# breakout_KL27Z_QFP64.net
KiCad netlist of a schematic drawn in EAGLE
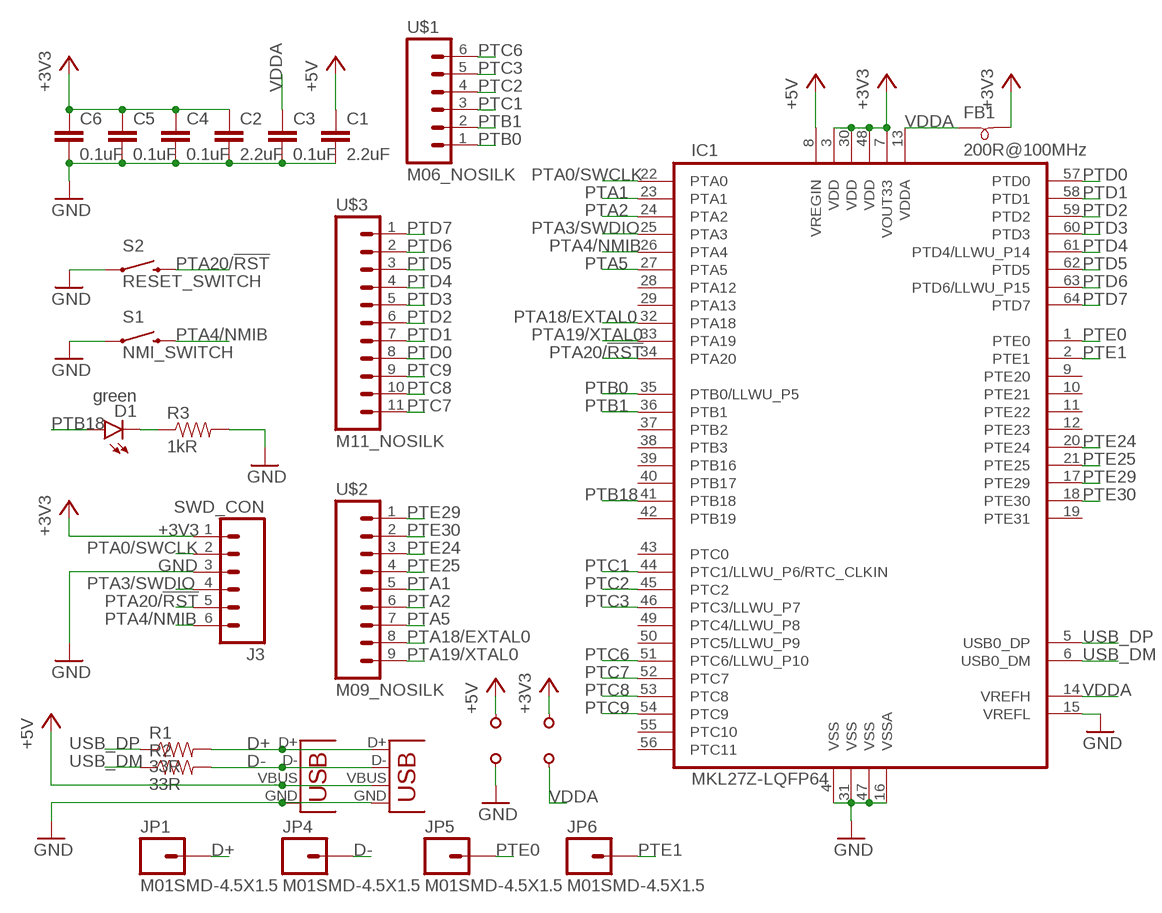
[diagram p0: schematic, sheet 1]

(export (version "E")
  (design (tool "Eeschema 10.0.6"))
  (components
    (comp (ref "C1")
      (value "2.2uF")
      (footprint "eagle-import:0805")
      (libsource (lib "eagle-import") (part "CAPACITOR0805"))
    )
    (comp (ref "C2")
      (value "2.2uF")
      (footprint "eagle-import:0805")
      (libsource (lib "eagle-import") (part "CAPACITOR0805"))
    )
    (comp (ref "C3")
      (value "0.1uF")
      (footprint "eagle-import:0805")
      (libsource (lib "eagle-import") (part "CAPACITOR0805"))
    )
    (comp (ref "C4")
      (value "0.1uF")
      (footprint "eagle-import:0805")
      (libsource (lib "eagle-import") (part "CAPACITOR0805"))
    )
    (comp (ref "C5")
      (value "0.1uF")
      (footprint "eagle-import:0805")
      (libsource (lib "eagle-import") (part "CAPACITOR0805"))
    )
    (comp (ref "C6")
      (value "0.1uF")
      (footprint "eagle-import:0805")
      (libsource (lib "eagle-import") (part "CAPACITOR0805"))
    )
    (comp (ref "D1")
      (value "green")
      (footprint "eagle-import:LED-805")
      (libsource (lib "eagle-import") (part "LED805"))
    )
    (comp (ref "FB1")
      (value "200R@100MHz")
      (footprint "eagle-import:0805")
      (libsource (lib "eagle-import") (part "FERRITE-BEAD0805"))
    )
    (comp (ref "IC1")
      (value "MKL27Z-LQFP64")
      (footprint "eagle-import:TQFP-64-0.5")
      (libsource (lib "eagle-import") (part "MKL27Z-LQFP64"))
    )
    (comp (ref "J3")
      (value "SWD_CON")
      (footprint "eagle-import:M06_NOSILK_1SQ")
      (libsource (lib "eagle-import") (part "M06_NOSILK_1SQ"))
    )
    (comp (ref "JP1")
      (value "M01SMD-4.5X1.5")
      (footprint "eagle-import:PAD-1.5X4.5")
      (libsource (lib "eagle-import") (part "M01SMD-4.5X1.5"))
    )
    (comp (ref "JP2")
      (value "USBSMD")
      (footprint "eagle-import:USB-MINIB")
      (libsource (lib "eagle-import") (part "USBSMD"))
    )
    (comp (ref "JP3")
      (value "USB-MICROB")
      (footprint "eagle-import:USB-MICROB")
      (libsource (lib "eagle-import") (part "USB-MICROB"))
    )
    (comp (ref "JP4")
      (value "M01SMD-4.5X1.5")
      (footprint "eagle-import:PAD-1.5X4.5")
      (libsource (lib "eagle-import") (part "M01SMD-4.5X1.5"))
    )
    (comp (ref "JP5")
      (value "M01SMD-4.5X1.5")
      (footprint "eagle-import:PAD-1.5X4.5")
      (libsource (lib "eagle-import") (part "M01SMD-4.5X1.5"))
    )
    (comp (ref "JP6")
      (value "M01SMD-4.5X1.5")
      (footprint "eagle-import:PAD-1.5X4.5")
      (libsource (lib "eagle-import") (part "M01SMD-4.5X1.5"))
    )
    (comp (ref "R1")
      (value "33R")
      (footprint "eagle-import:0805")
      (libsource (lib "eagle-import") (part "RESISTOR0805"))
    )
    (comp (ref "R2")
      (value "33R")
      (footprint "eagle-import:0805")
      (libsource (lib "eagle-import") (part "RESISTOR0805"))
    )
    (comp (ref "R3")
      (value "1kR")
      (footprint "eagle-import:0805")
      (libsource (lib "eagle-import") (part "RESISTOR0805"))
    )
    (comp (ref "S1")
      (value "NMI_SWITCH")
      (footprint "eagle-import:TACTILE-SWITCH-SMD")
      (libsource (lib "eagle-import") (part "SWITCH-MOMENTARY-2SMD-REDUNDANT"))
    )
    (comp (ref "S2")
      (value "RESET_SWITCH")
      (footprint "eagle-import:TACTILE-SWITCH-SMD")
      (libsource (lib "eagle-import") (part "SWITCH-MOMENTARY-2SMD-REDUNDANT"))
    )
    (comp (ref "U$1")
      (value "M06_NOSILK")
      (footprint "eagle-import:M06_NOSILK")
      (libsource (lib "eagle-import") (part "M06_NOSILK"))
    )
    (comp (ref "U$2")
      (value "M09_NOSILK")
      (footprint "eagle-import:M09_NOSILK")
      (libsource (lib "eagle-import") (part "M09_NOSILK"))
    )
    (comp (ref "U$3")
      (value "M11_NOSILK")
      (footprint "eagle-import:M11_NOSILK")
      (libsource (lib "eagle-import") (part "M11_NOSILK"))
    )
    (comp (ref "U$4")
      (value "M01_1SQ")
      (footprint "eagle-import:M01_1SQ")
      (libsource (lib "eagle-import") (part "M01_1SQ"))
    )
    (comp (ref "U$5")
      (value "M01_1SQ")
      (footprint "eagle-import:M01_1SQ")
      (libsource (lib "eagle-import") (part "M01_1SQ"))
    )
    (comp (ref "U$6")
      (value "M01_NOSILK")
      (footprint "eagle-import:M01_NOSILK")
      (libsource (lib "eagle-import") (part "M01_NOSILK"))
    )
    (comp (ref "U$7")
      (value "M01_1SQ")
      (footprint "eagle-import:M01_1SQ")
      (libsource (lib "eagle-import") (part "M01_1SQ"))
    )
  )
  (nets
    (net (code "1") (name "+3V3") (class "Default")
      (node (ref "C2") (pin "1") (pinfunction "1_1") (pintype "passive"))
      (node (ref "C4") (pin "1") (pinfunction "1_1") (pintype "passive"))
      (node (ref "C5") (pin "1") (pinfunction "1_1") (pintype "passive"))
      (node (ref "C6") (pin "1") (pinfunction "1_1") (pintype "passive"))
      (node (ref "FB1") (pin "2") (pinfunction "2_2") (pintype "passive"))
      (node (ref "IC1") (pin "3") (pinfunction "VDD_3") (pintype "power_in"))
      (node (ref "IC1") (pin "30") (pinfunction "VDD_30") (pintype "power_in"))
      (node (ref "IC1") (pin "48") (pinfunction "VDD_48") (pintype "power_in"))
      (node (ref "IC1") (pin "7") (pinfunction "VOUT33_7") (pintype "power_in"))
      (node (ref "J3") (pin "1") (pinfunction "1_1") (pintype "passive"))
      (node (ref "U$5") (pin "1") (pinfunction "1_1") (pintype "bidirectional"))
    )
    (net (code "2") (name "+5V") (class "Default")
      (node (ref "C1") (pin "1") (pinfunction "1_1") (pintype "passive"))
      (node (ref "IC1") (pin "8") (pinfunction "VREGIN_8") (pintype "power_in"))
      (node (ref "JP2") (pin "VBUS") (pinfunction "VBUS_VBUS") (pintype "bidirectional"))
      (node (ref "JP3") (pin "VBUS") (pinfunction "VBUS_VBUS") (pintype "bidirectional"))
      (node (ref "U$4") (pin "1") (pinfunction "1_1") (pintype "bidirectional"))
    )
    (net (code "3") (name "/D+") (class "Default")
      (node (ref "JP1") (pin "P$1") (pinfunction "1_P$1") (pintype "passive"))
      (node (ref "JP2") (pin "D+") (pinfunction "D+_D+") (pintype "bidirectional"))
      (node (ref "JP3") (pin "D+") (pinfunction "D+_D+") (pintype "bidirectional"))
      (node (ref "R1") (pin "2") (pinfunction "2_2") (pintype "passive"))
    )
    (net (code "4") (name "/D-") (class "Default")
      (node (ref "JP2") (pin "D-") (pinfunction "D-_D-") (pintype "bidirectional"))
      (node (ref "JP3") (pin "D-") (pinfunction "D-_D-") (pintype "bidirectional"))
      (node (ref "JP4") (pin "P$1") (pinfunction "1_P$1") (pintype "passive"))
      (node (ref "R2") (pin "2") (pinfunction "2_2") (pintype "passive"))
    )
    (net (code "5") (name "/PTA0{slash}SWCLK") (class "Default")
      (node (ref "IC1") (pin "22") (pinfunction "PTA0_22") (pintype "bidirectional"))
      (node (ref "J3") (pin "2") (pinfunction "2_2") (pintype "passive"))
    )
    (net (code "6") (name "/PTA1") (class "Default")
      (node (ref "IC1") (pin "23") (pinfunction "PTA1_23") (pintype "bidirectional"))
      (node (ref "U$2") (pin "5") (pinfunction "5_5") (pintype "passive"))
    )
    (net (code "7") (name "/PTA2") (class "Default")
      (node (ref "IC1") (pin "24") (pinfunction "PTA2_24") (pintype "bidirectional"))
      (node (ref "U$2") (pin "6") (pinfunction "6_6") (pintype "passive"))
    )
    (net (code "8") (name "/PTA3{slash}SWDIO") (class "Default")
      (node (ref "IC1") (pin "25") (pinfunction "PTA3_25") (pintype "bidirectional"))
      (node (ref "J3") (pin "4") (pinfunction "4_4") (pintype "passive"))
    )
    (net (code "9") (name "/PTA4{slash}NMIB") (class "Default")
      (node (ref "IC1") (pin "26") (pinfunction "PTA4_26") (pintype "bidirectional"))
      (node (ref "J3") (pin "6") (pinfunction "6_6") (pintype "passive"))
      (node (ref "S1") (pin "3") (pinfunction "2_3") (pintype "passive"))
      (node (ref "S1") (pin "4") (pinfunction "2_4") (pintype "passive"))
    )
    (net (code "10") (name "/PTA5") (class "Default")
      (node (ref "IC1") (pin "27") (pinfunction "PTA5_27") (pintype "bidirectional"))
      (node (ref "U$2") (pin "7") (pinfunction "7_7") (pintype "passive"))
    )
    (net (code "11") (name "/PTA18{slash}EXTAL0") (class "Default")
      (node (ref "IC1") (pin "32") (pinfunction "PTA18_32") (pintype "bidirectional"))
      (node (ref "U$2") (pin "8") (pinfunction "8_8") (pintype "passive"))
    )
    (net (code "12") (name "/PTA19{slash}XTAL0") (class "Default")
      (node (ref "IC1") (pin "33") (pinfunction "PTA19_33") (pintype "bidirectional"))
      (node (ref "U$2") (pin "9") (pinfunction "9_9") (pintype "passive"))
    )
    (net (code "13") (name "/PTA20{slash}~{RST}") (class "Default")
      (node (ref "IC1") (pin "34") (pinfunction "PTA20_34") (pintype "bidirectional"))
      (node (ref "J3") (pin "5") (pinfunction "5_5") (pintype "passive"))
      (node (ref "S2") (pin "3") (pinfunction "2_3") (pintype "passive"))
      (node (ref "S2") (pin "4") (pinfunction "2_4") (pintype "passive"))
    )
    (net (code "14") (name "/PTB0") (class "Default")
      (node (ref "IC1") (pin "35") (pinfunction "PTB0/LLWU_P5_35") (pintype "bidirectional"))
      (node (ref "U$1") (pin "1") (pinfunction "1_1") (pintype "passive"))
    )
    (net (code "15") (name "/PTB1") (class "Default")
      (node (ref "IC1") (pin "36") (pinfunction "PTB1_36") (pintype "bidirectional"))
      (node (ref "U$1") (pin "2") (pinfunction "2_2") (pintype "passive"))
    )
    (net (code "16") (name "/PTB18") (class "Default")
      (node (ref "D1") (pin "A") (pinfunction "A_A") (pintype "passive"))
      (node (ref "IC1") (pin "41") (pinfunction "PTB18_41") (pintype "bidirectional"))
    )
    (net (code "17") (name "/PTC1") (class "Default")
      (node (ref "IC1") (pin "44") (pinfunction "PTC1/LLWU_P6/RTC_CLKIN_44") (pintype "bidirectional"))
      (node (ref "U$1") (pin "3") (pinfunction "3_3") (pintype "passive"))
    )
    (net (code "18") (name "/PTC2") (class "Default")
      (node (ref "IC1") (pin "45") (pinfunction "PTC2_45") (pintype "bidirectional"))
      (node (ref "U$1") (pin "4") (pinfunction "4_4") (pintype "passive"))
    )
    (net (code "19") (name "/PTC3") (class "Default")
      (node (ref "IC1") (pin "46") (pinfunction "PTC3/LLWU_P7_46") (pintype "bidirectional"))
      (node (ref "U$1") (pin "5") (pinfunction "5_5") (pintype "passive"))
    )
    (net (code "20") (name "/PTC6") (class "Default")
      (node (ref "IC1") (pin "51") (pinfunction "PTC6/LLWU_P10_51") (pintype "bidirectional"))
      (node (ref "U$1") (pin "6") (pinfunction "6_6") (pintype "passive"))
    )
    (net (code "21") (name "/PTC7") (class "Default")
      (node (ref "IC1") (pin "52") (pinfunction "PTC7_52") (pintype "bidirectional"))
      (node (ref "U$3") (pin "11") (pinfunction "11_11") (pintype "passive"))
    )
    (net (code "22") (name "/PTC8") (class "Default")
      (node (ref "IC1") (pin "53") (pinfunction "PTC8_53") (pintype "bidirectional"))
      (node (ref "U$3") (pin "10") (pinfunction "10_10") (pintype "passive"))
    )
    (net (code "23") (name "/PTC9") (class "Default")
      (node (ref "IC1") (pin "54") (pinfunction "PTC9_54") (pintype "bidirectional"))
      (node (ref "U$3") (pin "9") (pinfunction "9_9") (pintype "passive"))
    )
    (net (code "24") (name "/PTD0") (class "Default")
      (node (ref "IC1") (pin "57") (pinfunction "PTD0_57") (pintype "bidirectional"))
      (node (ref "U$3") (pin "8") (pinfunction "8_8") (pintype "passive"))
    )
    (net (code "25") (name "/PTD1") (class "Default")
      (node (ref "IC1") (pin "58") (pinfunction "PTD1_58") (pintype "bidirectional"))
      (node (ref "U$3") (pin "7") (pinfunction "7_7") (pintype "passive"))
    )
    (net (code "26") (name "/PTD2") (class "Default")
      (node (ref "IC1") (pin "59") (pinfunction "PTD2_59") (pintype "bidirectional"))
      (node (ref "U$3") (pin "6") (pinfunction "6_6") (pintype "passive"))
    )
    (net (code "27") (name "/PTD3") (class "Default")
      (node (ref "IC1") (pin "60") (pinfunction "PTD3_60") (pintype "bidirectional"))
      (node (ref "U$3") (pin "5") (pinfunction "5_5") (pintype "passive"))
    )
    (net (code "28") (name "/PTD4") (class "Default")
      (node (ref "IC1") (pin "61") (pinfunction "PTD4/LLWU_P14_61") (pintype "bidirectional"))
      (node (ref "U$3") (pin "4") (pinfunction "4_4") (pintype "passive"))
    )
    (net (code "29") (name "/PTD5") (class "Default")
      (node (ref "IC1") (pin "62") (pinfunction "PTD5_62") (pintype "bidirectional"))
      (node (ref "U$3") (pin "3") (pinfunction "3_3") (pintype "passive"))
    )
    (net (code "30") (name "/PTD6") (class "Default")
      (node (ref "IC1") (pin "63") (pinfunction "PTD6/LLWU_P15_63") (pintype "bidirectional"))
      (node (ref "U$3") (pin "2") (pinfunction "2_2") (pintype "passive"))
    )
    (net (code "31") (name "/PTD7") (class "Default")
      (node (ref "IC1") (pin "64") (pinfunction "PTD7_64") (pintype "bidirectional"))
      (node (ref "U$3") (pin "1") (pinfunction "1_1") (pintype "passive"))
    )
    (net (code "32") (name "/PTE0") (class "Default")
      (node (ref "IC1") (pin "1") (pinfunction "PTE0_1") (pintype "bidirectional"))
      (node (ref "JP5") (pin "P$1") (pinfunction "1_P$1") (pintype "passive"))
    )
    (net (code "33") (name "/PTE1") (class "Default")
      (node (ref "IC1") (pin "2") (pinfunction "PTE1_2") (pintype "bidirectional"))
      (node (ref "JP6") (pin "P$1") (pinfunction "1_P$1") (pintype "passive"))
    )
    (net (code "34") (name "/PTE24") (class "Default")
      (node (ref "IC1") (pin "20") (pinfunction "PTE24_20") (pintype "bidirectional"))
      (node (ref "U$2") (pin "3") (pinfunction "3_3") (pintype "passive"))
    )
    (net (code "35") (name "/PTE25") (class "Default")
      (node (ref "IC1") (pin "21") (pinfunction "PTE25_21") (pintype "bidirectional"))
      (node (ref "U$2") (pin "4") (pinfunction "4_4") (pintype "passive"))
    )
    (net (code "36") (name "/PTE29") (class "Default")
      (node (ref "IC1") (pin "17") (pinfunction "PTE29_17") (pintype "bidirectional"))
      (node (ref "U$2") (pin "1") (pinfunction "1_1") (pintype "passive"))
    )
    (net (code "37") (name "/PTE30") (class "Default")
      (node (ref "IC1") (pin "18") (pinfunction "PTE30_18") (pintype "bidirectional"))
      (node (ref "U$2") (pin "2") (pinfunction "2_2") (pintype "passive"))
    )
    (net (code "38") (name "/USB_DM") (class "Default")
      (node (ref "IC1") (pin "6") (pinfunction "USB0_DM_6") (pintype "bidirectional"))
      (node (ref "R2") (pin "1") (pinfunction "1_1") (pintype "passive"))
    )
    (net (code "39") (name "/USB_DP") (class "Default")
      (node (ref "IC1") (pin "5") (pinfunction "USB0_DP_5") (pintype "bidirectional"))
      (node (ref "R1") (pin "1") (pinfunction "1_1") (pintype "passive"))
    )
    (net (code "40") (name "/VDDA") (class "Default")
      (node (ref "C3") (pin "1") (pinfunction "1_1") (pintype "passive"))
      (node (ref "FB1") (pin "1") (pinfunction "1_1") (pintype "passive"))
      (node (ref "IC1") (pin "13") (pinfunction "VDDA_13") (pintype "power_in"))
      (node (ref "IC1") (pin "14") (pinfunction "VREFH_14") (pintype "bidirectional"))
      (node (ref "U$7") (pin "1") (pinfunction "1_1") (pintype "bidirectional"))
    )
    (net (code "41") (name "GND") (class "Default")
      (node (ref "C1") (pin "2") (pinfunction "2_2") (pintype "passive"))
      (node (ref "C2") (pin "2") (pinfunction "2_2") (pintype "passive"))
      (node (ref "C3") (pin "2") (pinfunction "2_2") (pintype "passive"))
      (node (ref "C4") (pin "2") (pinfunction "2_2") (pintype "passive"))
      (node (ref "C5") (pin "2") (pinfunction "2_2") (pintype "passive"))
      (node (ref "C6") (pin "2") (pinfunction "2_2") (pintype "passive"))
      (node (ref "IC1") (pin "15") (pinfunction "VREFL_15") (pintype "bidirectional"))
      (node (ref "IC1") (pin "16") (pinfunction "VSSA_16") (pintype "power_in"))
      (node (ref "IC1") (pin "31") (pinfunction "VSS_31") (pintype "power_in"))
      (node (ref "IC1") (pin "4") (pinfunction "VSS_4") (pintype "power_in"))
      (node (ref "IC1") (pin "47") (pinfunction "VSS_47") (pintype "power_in"))
      (node (ref "J3") (pin "3") (pinfunction "3_3") (pintype "passive"))
      (node (ref "JP2") (pin "GND") (pinfunction "GND_GND") (pintype "bidirectional"))
      (node (ref "JP3") (pin "GND") (pinfunction "GND_GND") (pintype "bidirectional"))
      (node (ref "R3") (pin "2") (pinfunction "2_2") (pintype "passive"))
      (node (ref "S1") (pin "1") (pinfunction "1_1") (pintype "passive"))
      (node (ref "S1") (pin "2") (pinfunction "1_2") (pintype "passive"))
      (node (ref "S2") (pin "1") (pinfunction "1_1") (pintype "passive"))
      (node (ref "S2") (pin "2") (pinfunction "1_2") (pintype "passive"))
      (node (ref "U$6") (pin "1") (pinfunction "1_1") (pintype "bidirectional"))
    )
    (net (code "42") (name "Net-(D1-PadC)") (class "Default")
      (node (ref "D1") (pin "C") (pinfunction "C_C") (pintype "passive"))
      (node (ref "R3") (pin "1") (pinfunction "1_1") (pintype "passive"))
    )
    (net (code "43") (name "unconnected-(IC1-PTA12-Pad28)") (class "Default")
      (node (ref "IC1") (pin "28") (pinfunction "PTA12_28") (pintype "bidirectional"))
    )
    (net (code "44") (name "unconnected-(IC1-PTA13-Pad29)") (class "Default")
      (node (ref "IC1") (pin "29") (pinfunction "PTA13_29") (pintype "bidirectional"))
    )
    (net (code "45") (name "unconnected-(IC1-PTB2-Pad37)") (class "Default")
      (node (ref "IC1") (pin "37") (pinfunction "PTB2_37") (pintype "bidirectional"))
    )
    (net (code "46") (name "unconnected-(IC1-PTB3-Pad38)") (class "Default")
      (node (ref "IC1") (pin "38") (pinfunction "PTB3_38") (pintype "bidirectional"))
    )
    (net (code "47") (name "unconnected-(IC1-PTB16-Pad39)") (class "Default")
      (node (ref "IC1") (pin "39") (pinfunction "PTB16_39") (pintype "bidirectional"))
    )
    (net (code "48") (name "unconnected-(IC1-PTB17-Pad40)") (class "Default")
      (node (ref "IC1") (pin "40") (pinfunction "PTB17_40") (pintype "bidirectional"))
    )
    (net (code "49") (name "unconnected-(IC1-PTB19-Pad42)") (class "Default")
      (node (ref "IC1") (pin "42") (pinfunction "PTB19_42") (pintype "bidirectional"))
    )
    (net (code "50") (name "unconnected-(IC1-PTC0-Pad43)") (class "Default")
      (node (ref "IC1") (pin "43") (pinfunction "PTC0_43") (pintype "bidirectional"))
    )
    (net (code "51") (name "unconnected-(IC1-PTC4{slash}LLWU_P8-Pad49)") (class "Default")
      (node (ref "IC1") (pin "49") (pinfunction "PTC4/LLWU_P8_49") (pintype "bidirectional"))
    )
    (net (code "52") (name "unconnected-(IC1-PTC5{slash}LLWU_P9-Pad50)") (class "Default")
      (node (ref "IC1") (pin "50") (pinfunction "PTC5/LLWU_P9_50") (pintype "bidirectional"))
    )
    (net (code "53") (name "unconnected-(IC1-PTC10-Pad55)") (class "Default")
      (node (ref "IC1") (pin "55") (pinfunction "PTC10_55") (pintype "bidirectional"))
    )
    (net (code "54") (name "unconnected-(IC1-PTC11-Pad56)") (class "Default")
      (node (ref "IC1") (pin "56") (pinfunction "PTC11_56") (pintype "bidirectional"))
    )
    (net (code "55") (name "unconnected-(IC1-PTE20-Pad9)") (class "Default")
      (node (ref "IC1") (pin "9") (pinfunction "PTE20_9") (pintype "bidirectional"))
    )
    (net (code "56") (name "unconnected-(IC1-PTE21-Pad10)") (class "Default")
      (node (ref "IC1") (pin "10") (pinfunction "PTE21_10") (pintype "bidirectional"))
    )
    (net (code "57") (name "unconnected-(IC1-PTE22-Pad11)") (class "Default")
      (node (ref "IC1") (pin "11") (pinfunction "PTE22_11") (pintype "bidirectional"))
    )
    (net (code "58") (name "unconnected-(IC1-PTE23-Pad12)") (class "Default")
      (node (ref "IC1") (pin "12") (pinfunction "PTE23_12") (pintype "bidirectional"))
    )
    (net (code "59") (name "unconnected-(IC1-PTE31-Pad19)") (class "Default")
      (node (ref "IC1") (pin "19") (pinfunction "PTE31_19") (pintype "bidirectional"))
    )
  )
)
